# Sheet1.net
KiCad netlist of a schematic drawn in Altium Designer
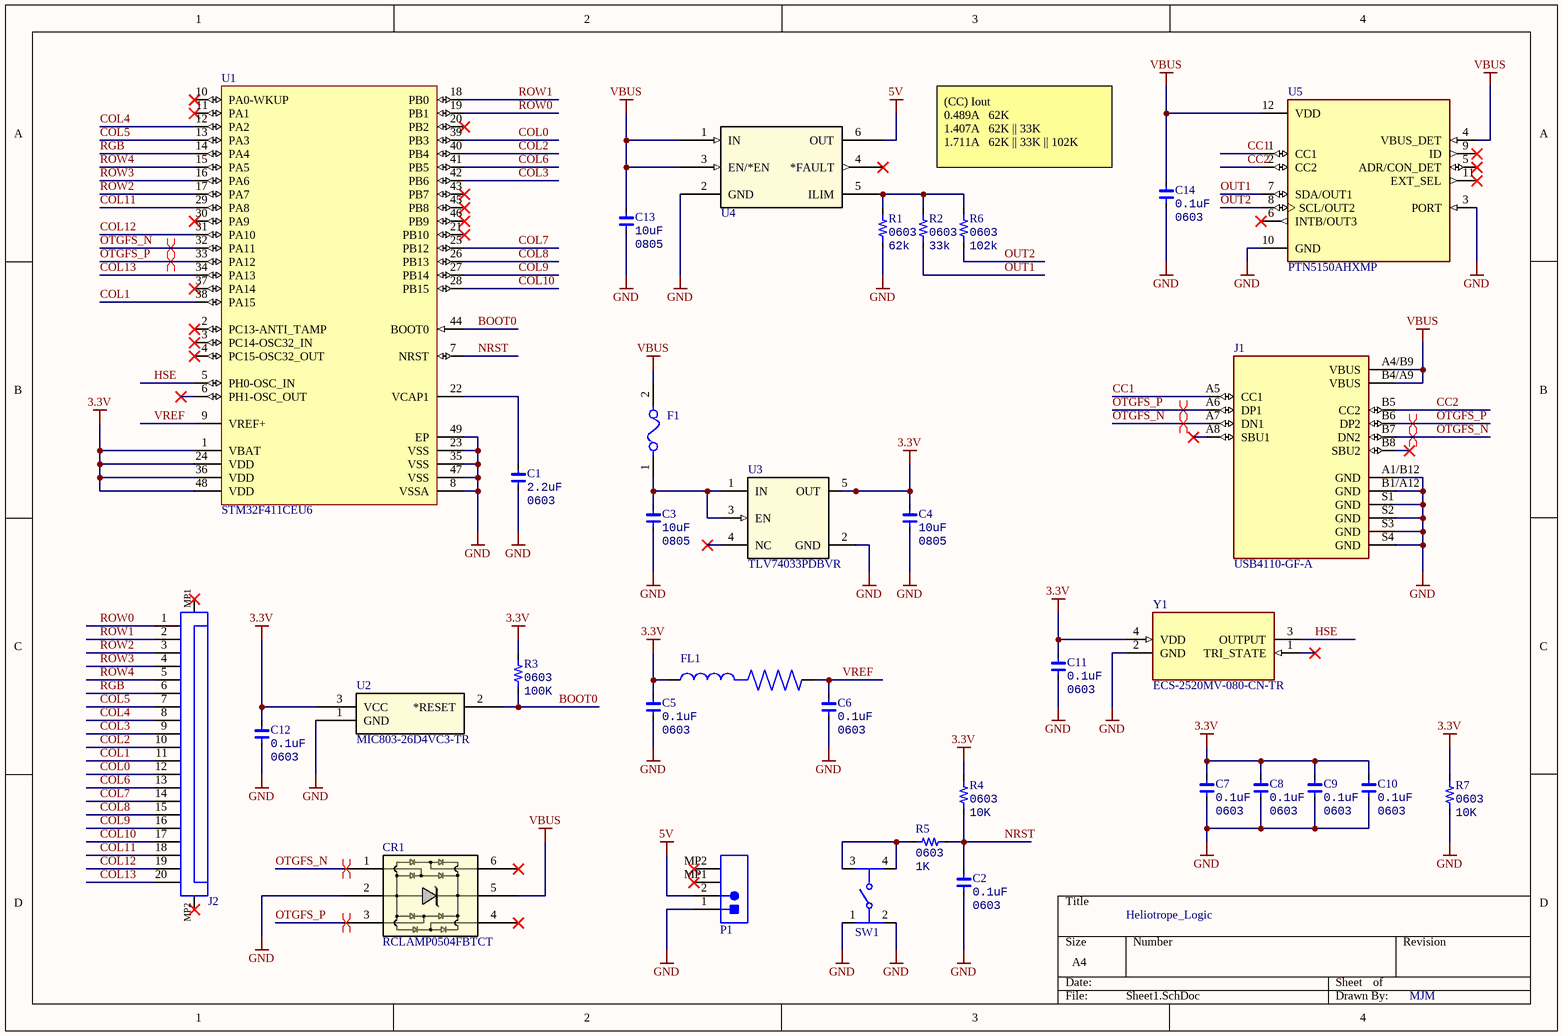
[diagram p0: Sheet1.SchDoc]

(export (version "E")
  (design (tool "Eeschema 10.0.6"))
  (components
    (comp (ref "C1")
      (value "2.2uF")
      (footprint "FP-CC0603-DA-MFG")
      (description "Cap Ceramic 2.2uF 10V X7R 10% SMD 0603 125C Paper T/R")
      (fields (field (name "TYPE") "0603") (field (name "Comment") "CC0603KRX7R6BB225"))
      (libsource (lib "Microcom Corporation") (part "M_Cap"))
    )
    (comp (ref "C2")
      (value "0.1uF")
      (footprint "FP-CC0603-DA-MFG")
      (description "0603 0.1 uF 50 V ±5 % Tolerance X7R SMT Multilayer Ceramic Capacitor")
      (fields (field (name "TYPE") "0603") (field (name "Comment") "CC0603JRX7R9BB104"))
      (libsource (lib "Microcom Corporation") (part "M_Cap"))
    )
    (comp (ref "C3")
      (value "10uF")
      (footprint "FP-GRM21B-0_15-MFG")
      (description "Cap Ceramic 10uF 10V X7R 10% Pad SMD 0805 125C T/R")
      (fields (field (name "TYPE") "0805") (field (name "Comment") "GRM21BR71A106KA73K"))
      (libsource (lib "Microcom Corporation") (part "M_Cap"))
    )
    (comp (ref "C4")
      (value "10uF")
      (footprint "FP-GRM21B-0_15-MFG")
      (description "Cap Ceramic 10uF 10V X7R 10% Pad SMD 0805 125C T/R")
      (fields (field (name "TYPE") "0805") (field (name "Comment") "GRM21BR71A106KA73K"))
      (libsource (lib "Microcom Corporation") (part "M_Cap"))
    )
    (comp (ref "C5")
      (value "0.1uF")
      (footprint "FP-CC0603-DA-MFG")
      (description "0603 0.1 uF 50 V ±5 % Tolerance X7R SMT Multilayer Ceramic Capacitor")
      (fields (field (name "TYPE") "0603") (field (name "Comment") "CC0603JRX7R9BB104"))
      (libsource (lib "Microcom Corporation") (part "M_Cap"))
    )
    (comp (ref "C6")
      (value "0.1uF")
      (footprint "FP-CC0603-DA-MFG")
      (description "0603 0.1 uF 50 V ±5 % Tolerance X7R SMT Multilayer Ceramic Capacitor")
      (fields (field (name "TYPE") "0603") (field (name "Comment") "CC0603JRX7R9BB104"))
      (libsource (lib "Microcom Corporation") (part "M_Cap"))
    )
    (comp (ref "C7")
      (value "0.1uF")
      (footprint "FP-CC0603-DA-MFG")
      (description "0603 0.1 uF 50 V ±5 % Tolerance X7R SMT Multilayer Ceramic Capacitor")
      (fields (field (name "TYPE") "0603") (field (name "Comment") "CC0603JRX7R9BB104"))
      (libsource (lib "Microcom Corporation") (part "M_Cap"))
    )
    (comp (ref "C8")
      (value "0.1uF")
      (footprint "FP-CC0603-DA-MFG")
      (description "0603 0.1 uF 50 V ±5 % Tolerance X7R SMT Multilayer Ceramic Capacitor")
      (fields (field (name "TYPE") "0603") (field (name "Comment") "CC0603JRX7R9BB104"))
      (libsource (lib "Microcom Corporation") (part "M_Cap"))
    )
    (comp (ref "C9")
      (value "0.1uF")
      (footprint "FP-CC0603-DA-MFG")
      (description "0603 0.1 uF 50 V ±5 % Tolerance X7R SMT Multilayer Ceramic Capacitor")
      (fields (field (name "TYPE") "0603") (field (name "Comment") "CC0603JRX7R9BB104"))
      (libsource (lib "Microcom Corporation") (part "M_Cap"))
    )
    (comp (ref "C10")
      (value "0.1uF")
      (footprint "FP-CC0603-DA-MFG")
      (description "0603 0.1 uF 50 V ±5 % Tolerance X7R SMT Multilayer Ceramic Capacitor")
      (fields (field (name "TYPE") "0603") (field (name "Comment") "CC0603JRX7R9BB104"))
      (libsource (lib "Microcom Corporation") (part "M_Cap"))
    )
    (comp (ref "C11")
      (value "0.1uF")
      (footprint "FP-CC0603-DA-MFG")
      (description "0603 0.1 uF 50 V ±5 % Tolerance X7R SMT Multilayer Ceramic Capacitor")
      (fields (field (name "TYPE") "0603") (field (name "Comment") "CC0603JRX7R9BB104"))
      (libsource (lib "Microcom Corporation") (part "M_Cap"))
    )
    (comp (ref "C12")
      (value "0.1uF")
      (footprint "FP-CC0603-DA-MFG")
      (description "0603 0.1 uF 50 V ±5 % Tolerance X7R SMT Multilayer Ceramic Capacitor")
      (fields (field (name "TYPE") "0603") (field (name "Comment") "CC0603JRX7R9BB104"))
      (libsource (lib "Microcom Corporation") (part "M_Cap"))
    )
    (comp (ref "C13")
      (value "10uF")
      (footprint "FP-GRM21B-0_15-MFG")
      (description "Cap Ceramic 10uF 10V X7R 10% Pad SMD 0805 125C T/R")
      (fields (field (name "TYPE") "0805") (field (name "Comment") "GRM21BR71A106KA73K"))
      (libsource (lib "Microcom Corporation") (part "M_Cap"))
    )
    (comp (ref "C14")
      (value "0.1uF")
      (footprint "FP-CC0603-DA-MFG")
      (description "0603 0.1 uF 50 V ±5 % Tolerance X7R SMT Multilayer Ceramic Capacitor")
      (fields (field (name "TYPE") "0603") (field (name "Comment") "CC0603JRX7R9BB104"))
      (libsource (lib "Microcom Corporation") (part "M_Cap"))
    )
    (comp (ref "CR1")
      (value "RCLAMP0504FBTCT")
      (footprint "SC70_RCLAMP_SEM")
      (description "ESD Suppressor TVS Quad Uni-Dir 30kV 6-Pin SC-70 T/R")
      (fields (field (name "COPYRIGHT") "Copyright (C) 2022 Ultra Librarian. All rights reserved."))
      (libsource (lib "Microcom Corporation") (part "RCLAMP0504FBTCT"))
    )
    (comp (ref "F1")
      (value "0603L010YR")
      (footprint "FP-0603L-MFG")
      (description "15VDC 100mA")
      (libsource (lib "Microcom Corporation") (part "5bcf9b9f640e542cf0359d10258e979"))
    )
    (comp (ref "FL1")
      (value "BLM18AG601SN1D")
      (footprint "BEADC1608X95N")
      (description "600 Ohms @ 100MHz 1 Ferrite Bead 0603 _1608 Metric_ 500mA 380mOhm")
      (fields (field (name "DIGI-KEY_PART_NUMBER") "490-1014-1-ND") (field (name "MANUFACTURER") "Murata"))
      (libsource (lib "Microcom Corporation") (part "BLM18AG601SN1D"))
    )
    (comp (ref "J1")
      (value "USB4110-GF-A")
      (footprint "GCT_USB4110-GF-A_REVB")
      (description "Conn USB Type C RCP 16 POS 0.3mm/0.5mm Solder ST SMD 16 Terminal 1 Port T/R")
      (libsource (lib "Microcom Corporation") (part "USB4110-GF-A_REVB"))
    )
    (comp (ref "J2")
      (value "68712014522")
      (footprint "68712014522")
      (description "Ffc / Fpc Board Connector, Zif, Surface Mount, Plug, 20, Bottom, 0.5 Mm Rohs Compliant: Yes")
      (fields (field (name "MF") "Wurth Electronics"))
      (libsource (lib "Microcom Corporation") (part "WE-68X1201XXX22-20"))
    )
    (comp (ref "P1")
      (value "53261-0271")
      (footprint "MOLX-53261-0271_V")
      (description "1.25mm Pitch PicoBlade™ Header, Surface Mount, Right Angle, Lead-Free, 2 Circuits")
      (libsource (lib "Microcom Corporation") (part "CN-1P-2M-R2"))
    )
    (comp (ref "R1")
      (value "62k")
      (footprint "FP-RMCF0603-MFG")
      (description "Res Thick Film 0603 62K Ohm 1% 1/10W ±100ppm/°C Molded SMD SMD Paper T/R")
      (fields (field (name "TYPE") "0603") (field (name "Comment") "RMCF0603FT62K0"))
      (libsource (lib "Microcom Corporation") (part "M_Res"))
    )
    (comp (ref "R2")
      (value "33k")
      (footprint "FP-RMCF0603-MFG")
      (description "Res Thick Film 0603 33K Ohm 1% 0.1W(1/10W) ±100ppm/C Pad SMD Automotive T/R")
      (fields (field (name "TYPE") "0603") (field (name "Comment") "RMCF0603FT33K0"))
      (libsource (lib "Microcom Corporation") (part "M_Res"))
    )
    (comp (ref "R3")
      (value "100K")
      (footprint "FP-RMCF0603-MFG")
      (description "Res Thick Film 0603 100K Ohm 5% 1/10W ±200ppm/°C Molded SMD Paper T/R")
      (fields (field (name "TYPE") "0603") (field (name "Comment") "RMCF0603JT100K"))
      (libsource (lib "Microcom Corporation") (part "M_Res"))
    )
    (comp (ref "R4")
      (value "10K")
      (footprint "FP-RMCF0603-MFG")
      (description "Res Thick Film 0603 10K Ohm 5% 1/10W ±100ppm/°C Molded SMD SMD Paper T/R")
      (fields (field (name "TYPE") "0603") (field (name "Comment") "RMCF0603JT10K0"))
      (libsource (lib "Microcom Corporation") (part "M_Res"))
    )
    (comp (ref "R5")
      (value "1K")
      (footprint "FP-RMCF0603-MFG")
      (description "Res Thick Film 0603 1K Ohm 5% 1/10W ±200ppm/°C Molded SMD Paper T/R")
      (fields (field (name "TYPE") "0603") (field (name "Comment") "RMCF0603JT1K00"))
      (libsource (lib "Microcom Corporation") (part "M_Res"))
    )
    (comp (ref "R6")
      (value "102k")
      (footprint "FP-RMCF0603-MFG")
      (description "Res Thick Film 0603 102K Ohm 1% 1/10W ±100ppm/°C Molded SMD SMD Paper T/R")
      (fields (field (name "TYPE") "0603") (field (name "Comment") "RMCF0603FT102K"))
      (libsource (lib "Microcom Corporation") (part "M_Res"))
    )
    (comp (ref "R7")
      (value "10K")
      (footprint "FP-RMCF0603-MFG")
      (description "Res Thick Film 0603 10K Ohm 5% 1/10W ±100ppm/°C Molded SMD SMD Paper T/R")
      (fields (field (name "TYPE") "0603") (field (name "Comment") "RMCF0603JT10K0"))
      (libsource (lib "Microcom Corporation") (part "M_Res"))
    )
    (comp (ref "SW1")
      (value "PTS526SK15SMTR2LFS")
      (footprint "FP-PTS526SK15SMTR2LFS-MFG")
      (description "Switch Tactile N.O. SPST Round Button Gull Wing 0.05A 12VDC 200000Cycles 2.55N SMD T/R")
      (libsource (lib "Microcom Corporation") (part "b8895f3f4cefb76e1819d2863dba89b"))
    )
    (comp (ref "U1")
      (value "STM32F411CEU6")
      (footprint "STM-UFQFPN48_M")
      (description "ARM® Cortex®-M4 STM32 F4 Microcontroller IC 32-Bit 100MHz 512KB (512K x 8) FLASH 48-UFQFPN (7x7)")
      (libsource (lib "Microcom Corporation") (part "MC-ARM-STM32F411-UFQFPN48"))
    )
    (comp (ref "U2")
      (value "MIC803-26D4VC3-TR")
      (footprint "SC-70_C3_MCH")
      (description "3-Pin Microprocessor Supervisor Circuit w/ Open-Drain Reset Output")
      (fields (field (name "COPYRIGHT") "Copyright (C) 2022 Ultra Librarian. All rights reserved."))
      (libsource (lib "Microcom Corporation") (part "MIC803-26D4VC3-TR"))
    )
    (comp (ref "U3")
      (value "TLV74033PDBVR")
      (footprint "DBV0005A-IPC_A")
      (description "300-mA low-dropout (LDO) regulator with foldback current limit 5-SOT-23 -40 to 125")
      (fields (field (name "COPYRIGHT") "Copyright (C) 2022 Ultra Librarian. All rights reserved."))
      (libsource (lib "Microcom Corporation") (part "TLV74033PDBVR"))
    )
    (comp (ref "U4")
      (value "AP22653AW6-7")
      (footprint "SOT26-A1_DIO")
      (description "PRECISION ADJUSTABLE CURRENT-LIMITED POWER SWITCHES, -40 to 85°C pF, RoHS")
      (fields (field (name "COPYRIGHT") "Copyright (C) 2022 Ultra Librarian. All rights reserved."))
      (libsource (lib "Microcom Corporation") (part "AP22653AW6-7"))
    )
    (comp (ref "U5")
      (value "PTN5150AHXMP")
      (footprint "IC_PTN5150AHXMP")
      (description "PTN5150A Series 2.7 to 5.5 V CC Logic for USB Type-C Applications - XFQFN-12")
      (fields (field (name "DIGI-KEY_PART_NUMBER") "568-13083-2-ND") (field (name "MF") "NXP USA"))
      (libsource (lib "Microcom Corporation") (part "PTN5150AHXMP"))
    )
    (comp (ref "Y1")
      (value "ECS-2520MV-080-CN-TR")
      (footprint "OSC_ECS-2520S25-250-FN-TR")
      (description "ECS-2520MV Series 8MHz 2.5x2mm 3.6 V SMT HCMOS Multivolt Crystal Oscillator")
      (fields (field (name "MF") "ECS Inc.") (field (name "DIGI-KEY_PART_NUMBER") "XC3029CT-ND"))
      (libsource (lib "Microcom Corporation") (part "ECS-2520MV-080-CN-TR"))
    )
  )
  (nets
    (net (code "1") (name "/BOOT0") (class "Default")
      (node (ref "R3") (pin "1") (pinfunction "1_1") (pintype "passive"))
      (node (ref "U1") (pin "44") (pinfunction "BOOT0_44") (pintype "input"))
      (node (ref "U2") (pin "2") (pinfunction "*RESET_2") (pintype "passive"))
    )
    (net (code "2") (name "/CC1") (class "Default")
      (node (ref "J1") (pin "A5") (pinfunction "CC1_A5") (pintype "bidirectional"))
      (node (ref "U5") (pin "1") (pinfunction "CC1_1") (pintype "bidirectional"))
    )
    (net (code "3") (name "/CC2") (class "Default")
      (node (ref "J1") (pin "B5") (pinfunction "CC2_B5") (pintype "bidirectional"))
      (node (ref "U5") (pin "2") (pinfunction "CC2_2") (pintype "bidirectional"))
    )
    (net (code "4") (name "/COL0") (class "Default")
      (node (ref "J2") (pin "12") (pinfunction "12_12") (pintype "passive"))
      (node (ref "U1") (pin "39") (pinfunction "PB3_39") (pintype "bidirectional"))
    )
    (net (code "5") (name "/COL1") (class "Default")
      (node (ref "J2") (pin "11") (pinfunction "11_11") (pintype "passive"))
      (node (ref "U1") (pin "38") (pinfunction "PA15_38") (pintype "bidirectional"))
    )
    (net (code "6") (name "/COL2") (class "Default")
      (node (ref "J2") (pin "10") (pinfunction "10_10") (pintype "passive"))
      (node (ref "U1") (pin "40") (pinfunction "PB4_40") (pintype "bidirectional"))
    )
    (net (code "7") (name "/COL3") (class "Default")
      (node (ref "J2") (pin "9") (pinfunction "9_9") (pintype "passive"))
      (node (ref "U1") (pin "42") (pinfunction "PB6_42") (pintype "bidirectional"))
    )
    (net (code "8") (name "/COL4") (class "Default")
      (node (ref "J2") (pin "8") (pinfunction "8_8") (pintype "passive"))
      (node (ref "U1") (pin "12") (pinfunction "PA2_12") (pintype "bidirectional"))
    )
    (net (code "9") (name "/COL5") (class "Default")
      (node (ref "J2") (pin "7") (pinfunction "7_7") (pintype "passive"))
      (node (ref "U1") (pin "13") (pinfunction "PA3_13") (pintype "bidirectional"))
    )
    (net (code "10") (name "/COL6") (class "Default")
      (node (ref "J2") (pin "13") (pinfunction "13_13") (pintype "passive"))
      (node (ref "U1") (pin "41") (pinfunction "PB5_41") (pintype "bidirectional"))
    )
    (net (code "11") (name "/COL7") (class "Default")
      (node (ref "J2") (pin "14") (pinfunction "14_14") (pintype "passive"))
      (node (ref "U1") (pin "25") (pinfunction "PB12_25") (pintype "bidirectional"))
    )
    (net (code "12") (name "/COL8") (class "Default")
      (node (ref "J2") (pin "15") (pinfunction "15_15") (pintype "passive"))
      (node (ref "U1") (pin "26") (pinfunction "PB13_26") (pintype "bidirectional"))
    )
    (net (code "13") (name "/COL9") (class "Default")
      (node (ref "J2") (pin "16") (pinfunction "16_16") (pintype "passive"))
      (node (ref "U1") (pin "27") (pinfunction "PB14_27") (pintype "bidirectional"))
    )
    (net (code "14") (name "/COL10") (class "Default")
      (node (ref "J2") (pin "17") (pinfunction "17_17") (pintype "passive"))
      (node (ref "U1") (pin "28") (pinfunction "PB15_28") (pintype "bidirectional"))
    )
    (net (code "15") (name "/COL11") (class "Default")
      (node (ref "J2") (pin "18") (pinfunction "18_18") (pintype "passive"))
      (node (ref "U1") (pin "29") (pinfunction "PA8_29") (pintype "bidirectional"))
    )
    (net (code "16") (name "/COL12") (class "Default")
      (node (ref "J2") (pin "19") (pinfunction "19_19") (pintype "passive"))
      (node (ref "U1") (pin "31") (pinfunction "PA10_31") (pintype "bidirectional"))
    )
    (net (code "17") (name "/COL13") (class "Default")
      (node (ref "J2") (pin "20") (pinfunction "20_20") (pintype "passive"))
      (node (ref "U1") (pin "34") (pinfunction "PA13_34") (pintype "bidirectional"))
    )
    (net (code "18") (name "/HSE") (class "Default")
      (node (ref "U1") (pin "5") (pinfunction "PH0-OSC_IN_5") (pintype "bidirectional"))
      (node (ref "Y1") (pin "3") (pinfunction "OUTPUT_3") (pintype "passive"))
    )
    (net (code "19") (name "/NRST") (class "Default")
      (node (ref "C2") (pin "2") (pinfunction "2_2") (pintype "passive"))
      (node (ref "R4") (pin "1") (pinfunction "1_1") (pintype "passive"))
      (node (ref "R5") (pin "1") (pinfunction "1_1") (pintype "passive"))
      (node (ref "U1") (pin "7") (pinfunction "NRST_7") (pintype "bidirectional"))
    )
    (net (code "20") (name "/OTGFS_N") (class "Default")
      (node (ref "CR1") (pin "1") (pinfunction "1_1") (pintype "passive"))
      (node (ref "J1") (pin "A7") (pinfunction "DN1_A7") (pintype "bidirectional"))
      (node (ref "J1") (pin "B7") (pinfunction "DN2_B7") (pintype "bidirectional"))
      (node (ref "U1") (pin "32") (pinfunction "PA11_32") (pintype "bidirectional"))
    )
    (net (code "21") (name "/OTGFS_P") (class "Default")
      (node (ref "CR1") (pin "3") (pinfunction "3_3") (pintype "passive"))
      (node (ref "J1") (pin "A6") (pinfunction "DP1_A6") (pintype "bidirectional"))
      (node (ref "J1") (pin "B6") (pinfunction "DP2_B6") (pintype "bidirectional"))
      (node (ref "U1") (pin "33") (pinfunction "PA12_33") (pintype "bidirectional"))
    )
    (net (code "22") (name "/OUT1") (class "Default")
      (node (ref "R2") (pin "1") (pinfunction "1_1") (pintype "passive"))
      (node (ref "U5") (pin "7") (pinfunction "SDA/OUT1_7") (pintype "bidirectional"))
    )
    (net (code "23") (name "/OUT2") (class "Default")
      (node (ref "R6") (pin "1") (pinfunction "1_1") (pintype "passive"))
      (node (ref "U5") (pin "8") (pinfunction "SCL/OUT2_8") (pintype "bidirectional"))
    )
    (net (code "24") (name "/RGB") (class "Default")
      (node (ref "J2") (pin "6") (pinfunction "6_6") (pintype "passive"))
      (node (ref "U1") (pin "14") (pinfunction "PA4_14") (pintype "bidirectional"))
    )
    (net (code "25") (name "/ROW0") (class "Default")
      (node (ref "J2") (pin "1") (pinfunction "1_1") (pintype "passive"))
      (node (ref "U1") (pin "19") (pinfunction "PB1_19") (pintype "bidirectional"))
    )
    (net (code "26") (name "/ROW1") (class "Default")
      (node (ref "J2") (pin "2") (pinfunction "2_2") (pintype "passive"))
      (node (ref "U1") (pin "18") (pinfunction "PB0_18") (pintype "bidirectional"))
    )
    (net (code "27") (name "/ROW2") (class "Default")
      (node (ref "J2") (pin "3") (pinfunction "3_3") (pintype "passive"))
      (node (ref "U1") (pin "17") (pinfunction "PA7_17") (pintype "bidirectional"))
    )
    (net (code "28") (name "/ROW3") (class "Default")
      (node (ref "J2") (pin "4") (pinfunction "4_4") (pintype "passive"))
      (node (ref "U1") (pin "16") (pinfunction "PA6_16") (pintype "bidirectional"))
    )
    (net (code "29") (name "/ROW4") (class "Default")
      (node (ref "J2") (pin "5") (pinfunction "5_5") (pintype "passive"))
      (node (ref "U1") (pin "15") (pinfunction "PA5_15") (pintype "bidirectional"))
    )
    (net (code "30") (name "/VREF") (class "Default")
      (node (ref "C6") (pin "2") (pinfunction "2_2") (pintype "passive"))
      (node (ref "FL1") (pin "2") (pinfunction "2_2") (pintype "passive"))
      (node (ref "U1") (pin "9") (pinfunction "VREF+_9") (pintype "power_in"))
    )
    (net (code "31") (name "3.3V") (class "Default")
      (node (ref "C10") (pin "2") (pinfunction "2_2") (pintype "passive"))
      (node (ref "C11") (pin "2") (pinfunction "2_2") (pintype "passive"))
      (node (ref "C12") (pin "2") (pinfunction "2_2") (pintype "passive"))
      (node (ref "C4") (pin "2") (pinfunction "2_2") (pintype "passive"))
      (node (ref "C5") (pin "2") (pinfunction "2_2") (pintype "passive"))
      (node (ref "C7") (pin "2") (pinfunction "2_2") (pintype "passive"))
      (node (ref "C8") (pin "2") (pinfunction "2_2") (pintype "passive"))
      (node (ref "C9") (pin "2") (pinfunction "2_2") (pintype "passive"))
      (node (ref "FL1") (pin "1") (pinfunction "1_1") (pintype "passive"))
      (node (ref "R3") (pin "2") (pinfunction "2_2") (pintype "passive"))
      (node (ref "R4") (pin "2") (pinfunction "2_2") (pintype "passive"))
      (node (ref "R7") (pin "2") (pinfunction "2_2") (pintype "passive"))
      (node (ref "U1") (pin "1") (pinfunction "VBAT_1") (pintype "power_in"))
      (node (ref "U1") (pin "24") (pinfunction "VDD_24") (pintype "power_in"))
      (node (ref "U1") (pin "36") (pinfunction "VDD_36") (pintype "power_in"))
      (node (ref "U1") (pin "48") (pinfunction "VDD_48") (pintype "power_in"))
      (node (ref "U2") (pin "3") (pinfunction "VCC_3") (pintype "power_in"))
      (node (ref "U3") (pin "5") (pinfunction "OUT_5") (pintype "passive"))
      (node (ref "Y1") (pin "4") (pinfunction "VDD_4") (pintype "input"))
    )
    (net (code "32") (name "5V") (class "Default")
      (node (ref "P1") (pin "2") (pinfunction "2_2") (pintype "passive"))
      (node (ref "U4") (pin "6") (pinfunction "OUT_6") (pintype "passive"))
    )
    (net (code "33") (name "GND") (class "Default")
      (node (ref "C1") (pin "1") (pinfunction "1_1") (pintype "passive"))
      (node (ref "C10") (pin "1") (pinfunction "1_1") (pintype "passive"))
      (node (ref "C11") (pin "1") (pinfunction "1_1") (pintype "passive"))
      (node (ref "C12") (pin "1") (pinfunction "1_1") (pintype "passive"))
      (node (ref "C13") (pin "1") (pinfunction "1_1") (pintype "passive"))
      (node (ref "C14") (pin "1") (pinfunction "1_1") (pintype "passive"))
      (node (ref "C2") (pin "1") (pinfunction "1_1") (pintype "passive"))
      (node (ref "C3") (pin "1") (pinfunction "1_1") (pintype "passive"))
      (node (ref "C4") (pin "1") (pinfunction "1_1") (pintype "passive"))
      (node (ref "C5") (pin "1") (pinfunction "1_1") (pintype "passive"))
      (node (ref "C6") (pin "1") (pinfunction "1_1") (pintype "passive"))
      (node (ref "C7") (pin "1") (pinfunction "1_1") (pintype "passive"))
      (node (ref "C8") (pin "1") (pinfunction "1_1") (pintype "passive"))
      (node (ref "C9") (pin "1") (pinfunction "1_1") (pintype "passive"))
      (node (ref "CR1") (pin "2") (pinfunction "2_2") (pintype "passive"))
      (node (ref "J1") (pin "A1/B12") (pinfunction "GND_A1/B12") (pintype "power_in"))
      (node (ref "J1") (pin "B1/A12") (pinfunction "GND_B1/A12") (pintype "power_in"))
      (node (ref "J1") (pin "S1") (pinfunction "GND_S1") (pintype "power_in"))
      (node (ref "J1") (pin "S2") (pinfunction "GND_S2") (pintype "power_in"))
      (node (ref "J1") (pin "S3") (pinfunction "GND_S3") (pintype "power_in"))
      (node (ref "J1") (pin "S4") (pinfunction "GND_S4") (pintype "power_in"))
      (node (ref "P1") (pin "1") (pinfunction "1_1") (pintype "passive"))
      (node (ref "R1") (pin "1") (pinfunction "1_1") (pintype "passive"))
      (node (ref "R7") (pin "1") (pinfunction "1_1") (pintype "passive"))
      (node (ref "SW1") (pin "1") (pinfunction "1_1") (pintype "passive"))
      (node (ref "SW1") (pin "2") (pinfunction "2_2") (pintype "passive"))
      (node (ref "U1") (pin "23") (pinfunction "VSS_23") (pintype "power_in"))
      (node (ref "U1") (pin "35") (pinfunction "VSS_35") (pintype "power_in"))
      (node (ref "U1") (pin "47") (pinfunction "VSS_47") (pintype "power_in"))
      (node (ref "U1") (pin "49") (pinfunction "EP_49") (pintype "power_in"))
      (node (ref "U1") (pin "8") (pinfunction "VSSA_8") (pintype "power_in"))
      (node (ref "U2") (pin "1") (pinfunction "GND_1") (pintype "power_in"))
      (node (ref "U3") (pin "2") (pinfunction "GND_2") (pintype "power_in"))
      (node (ref "U4") (pin "2") (pinfunction "GND_2") (pintype "passive"))
      (node (ref "U5") (pin "10") (pinfunction "GND_10") (pintype "power_in"))
      (node (ref "U5") (pin "3") (pinfunction "PORT_3") (pintype "input"))
      (node (ref "Y1") (pin "2") (pinfunction "GND_2") (pintype "power_in"))
    )
    (net (code "34") (name "Net-(R5-Pad2)") (class "Default")
      (node (ref "R5") (pin "2") (pinfunction "2_2") (pintype "passive"))
      (node (ref "SW1") (pin "3") (pinfunction "3_3") (pintype "passive"))
      (node (ref "SW1") (pin "4") (pinfunction "4_4") (pintype "passive"))
    )
    (net (code "35") (name "Net-(U1-VCAP1)") (class "Default")
      (node (ref "C1") (pin "2") (pinfunction "2_2") (pintype "passive"))
      (node (ref "U1") (pin "22") (pinfunction "VCAP1_22") (pintype "passive"))
    )
    (net (code "36") (name "Net-(U3-EN)") (class "Default")
      (node (ref "C3") (pin "2") (pinfunction "2_2") (pintype "passive"))
      (node (ref "F1") (pin "1") (pinfunction "1_1") (pintype "passive"))
      (node (ref "U3") (pin "1") (pinfunction "IN_1") (pintype "power_in"))
      (node (ref "U3") (pin "3") (pinfunction "EN_3") (pintype "input"))
    )
    (net (code "37") (name "Net-(U4-ILIM)") (class "Default")
      (node (ref "R1") (pin "2") (pinfunction "2_2") (pintype "passive"))
      (node (ref "R2") (pin "2") (pinfunction "2_2") (pintype "passive"))
      (node (ref "R6") (pin "2") (pinfunction "2_2") (pintype "passive"))
      (node (ref "U4") (pin "5") (pinfunction "ILIM_5") (pintype "passive"))
    )
    (net (code "38") (name "VBUS") (class "Default")
      (node (ref "C13") (pin "2") (pinfunction "2_2") (pintype "passive"))
      (node (ref "C14") (pin "2") (pinfunction "2_2") (pintype "passive"))
      (node (ref "CR1") (pin "5") (pinfunction "5_5") (pintype "passive"))
      (node (ref "F1") (pin "2") (pinfunction "2_2") (pintype "passive"))
      (node (ref "J1") (pin "A4/B9") (pinfunction "VBUS_A4/B9") (pintype "power_in"))
      (node (ref "J1") (pin "B4/A9") (pinfunction "VBUS_B4/A9") (pintype "power_in"))
      (node (ref "U4") (pin "1") (pinfunction "IN_1") (pintype "input"))
      (node (ref "U4") (pin "3") (pinfunction "EN/*EN_3") (pintype "input"))
      (node (ref "U5") (pin "12") (pinfunction "VDD_12") (pintype "power_in"))
      (node (ref "U5") (pin "4") (pinfunction "VBUS_DET_4") (pintype "input"))
    )
    (net (code "39") (name "unconnected-(CR1-Pad4)") (class "Default")
      (node (ref "CR1") (pin "4") (pinfunction "4_4") (pintype "passive+no_connect"))
    )
    (net (code "40") (name "unconnected-(CR1-Pad6)") (class "Default")
      (node (ref "CR1") (pin "6") (pinfunction "6_6") (pintype "passive+no_connect"))
    )
    (net (code "41") (name "unconnected-(J1-SBU1-PadA8)") (class "Default")
      (node (ref "J1") (pin "A8") (pinfunction "SBU1_A8") (pintype "bidirectional+no_connect"))
    )
    (net (code "42") (name "unconnected-(J1-SBU2-PadB8)") (class "Default")
      (node (ref "J1") (pin "B8") (pinfunction "SBU2_B8") (pintype "bidirectional+no_connect"))
    )
    (net (code "43") (name "unconnected-(J2-PadMP1)") (class "Default")
      (node (ref "J2") (pin "MP1") (pinfunction "MP1_MP1") (pintype "passive+no_connect"))
    )
    (net (code "44") (name "unconnected-(J2-PadMP2)") (class "Default")
      (node (ref "J2") (pin "MP2") (pinfunction "MP2_MP2") (pintype "passive+no_connect"))
    )
    (net (code "45") (name "unconnected-(P1-PadMP1)") (class "Default")
      (node (ref "P1") (pin "MP1") (pinfunction "MP1_MP1") (pintype "passive+no_connect"))
    )
    (net (code "46") (name "unconnected-(P1-PadMP2)") (class "Default")
      (node (ref "P1") (pin "MP2") (pinfunction "MP2_MP2") (pintype "passive+no_connect"))
    )
    (net (code "47") (name "unconnected-(U1-PA0-WKUP-Pad10)") (class "Default")
      (node (ref "U1") (pin "10") (pinfunction "PA0-WKUP_10") (pintype "bidirectional+no_connect"))
    )
    (net (code "48") (name "unconnected-(U1-PA1-Pad11)") (class "Default")
      (node (ref "U1") (pin "11") (pinfunction "PA1_11") (pintype "bidirectional+no_connect"))
    )
    (net (code "49") (name "unconnected-(U1-PA9-Pad30)") (class "Default")
      (node (ref "U1") (pin "30") (pinfunction "PA9_30") (pintype "bidirectional+no_connect"))
    )
    (net (code "50") (name "unconnected-(U1-PA14-Pad37)") (class "Default")
      (node (ref "U1") (pin "37") (pinfunction "PA14_37") (pintype "bidirectional+no_connect"))
    )
    (net (code "51") (name "unconnected-(U1-PB2-Pad20)") (class "Default")
      (node (ref "U1") (pin "20") (pinfunction "PB2_20") (pintype "bidirectional+no_connect"))
    )
    (net (code "52") (name "unconnected-(U1-PB7-Pad43)") (class "Default")
      (node (ref "U1") (pin "43") (pinfunction "PB7_43") (pintype "bidirectional+no_connect"))
    )
    (net (code "53") (name "unconnected-(U1-PB8-Pad45)") (class "Default")
      (node (ref "U1") (pin "45") (pinfunction "PB8_45") (pintype "bidirectional+no_connect"))
    )
    (net (code "54") (name "unconnected-(U1-PB9-Pad46)") (class "Default")
      (node (ref "U1") (pin "46") (pinfunction "PB9_46") (pintype "bidirectional+no_connect"))
    )
    (net (code "55") (name "unconnected-(U1-PB10-Pad21)") (class "Default")
      (node (ref "U1") (pin "21") (pinfunction "PB10_21") (pintype "bidirectional+no_connect"))
    )
    (net (code "56") (name "unconnected-(U1-PC13-ANTI_TAMP-Pad2)") (class "Default")
      (node (ref "U1") (pin "2") (pinfunction "PC13-ANTI_TAMP_2") (pintype "bidirectional+no_connect"))
    )
    (net (code "57") (name "unconnected-(U1-PC14-OSC32_IN-Pad3)") (class "Default")
      (node (ref "U1") (pin "3") (pinfunction "PC14-OSC32_IN_3") (pintype "bidirectional+no_connect"))
    )
    (net (code "58") (name "unconnected-(U1-PC15-OSC32_OUT-Pad4)") (class "Default")
      (node (ref "U1") (pin "4") (pinfunction "PC15-OSC32_OUT_4") (pintype "bidirectional+no_connect"))
    )
    (net (code "59") (name "unconnected-(U1-PH1-OSC_OUT-Pad6)") (class "Default")
      (node (ref "U1") (pin "6") (pinfunction "PH1-OSC_OUT_6") (pintype "bidirectional+no_connect"))
    )
    (net (code "60") (name "unconnected-(U3-NC-Pad4)") (class "Default")
      (node (ref "U3") (pin "4") (pinfunction "NC_4") (pintype "passive+no_connect"))
    )
    (net (code "61") (name "unconnected-(U4-*FAULT-Pad4)") (class "Default")
      (node (ref "U4") (pin "4") (pinfunction "*FAULT_4") (pintype "output+no_connect"))
    )
    (net (code "62") (name "unconnected-(U5-ADR{slash}CON_DET-Pad5)") (class "Default")
      (node (ref "U5") (pin "5") (pinfunction "ADR/CON_DET_5") (pintype "bidirectional+no_connect"))
    )
    (net (code "63") (name "unconnected-(U5-EXT_SEL-Pad11)") (class "Default")
      (node (ref "U5") (pin "11") (pinfunction "EXT_SEL_11") (pintype "output+no_connect"))
    )
    (net (code "64") (name "unconnected-(U5-ID-Pad9)") (class "Default")
      (node (ref "U5") (pin "9") (pinfunction "ID_9") (pintype "output+no_connect"))
    )
    (net (code "65") (name "unconnected-(U5-INTB{slash}OUT3-Pad6)") (class "Default")
      (node (ref "U5") (pin "6") (pinfunction "INTB/OUT3_6") (pintype "output+no_connect"))
    )
    (net (code "66") (name "unconnected-(Y1-TRI_STATE-Pad1)") (class "Default")
      (node (ref "Y1") (pin "1") (pinfunction "TRI_STATE_1") (pintype "input+no_connect"))
    )
  )
)
